# pwr.net
KiCad netlist of a schematic drawn in Altium Designer
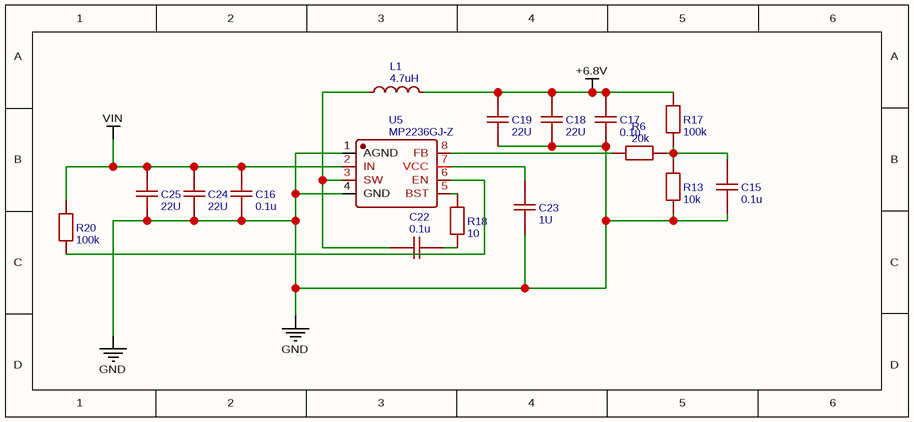
[diagram p0: pwr.schdoc]

(export (version "E")
  (design (tool "Eeschema 10.0.6"))
  (components
    (comp (ref "C15")
      (value "0.1u")
      (fields (field (name "CONTRIBUTOR") "LCEDA_Lib"))
      (libsource (lib "altium-import") (part "root_1_0.1u_"))
    )
    (comp (ref "C16")
      (value "0.1u")
      (fields (field (name "CONTRIBUTOR") "LCEDA_Lib"))
      (libsource (lib "altium-import") (part "root_1_0.1u_"))
    )
    (comp (ref "C17")
      (value "0.1u")
      (fields (field (name "CONTRIBUTOR") "LCEDA_Lib"))
      (libsource (lib "altium-import") (part "root_1_0.1u_"))
    )
    (comp (ref "C18")
      (value "22U")
      (fields (field (name "CONTRIBUTOR") "LCEDA_Lib"))
      (libsource (lib "altium-import") (part "root_1_22U_"))
    )
    (comp (ref "C19")
      (value "22U")
      (fields (field (name "CONTRIBUTOR") "LCEDA_Lib"))
      (libsource (lib "altium-import") (part "root_1_22U_"))
    )
    (comp (ref "C22")
      (value "0.1u")
      (fields (field (name "CONTRIBUTOR") "LCEDA_Lib"))
      (libsource (lib "altium-import") (part "root_0_0.1u_"))
    )
    (comp (ref "C23")
      (value "1U")
      (fields (field (name "CONTRIBUTOR") "LCEDA_Lib"))
      (libsource (lib "altium-import") (part "root_1_1U_"))
    )
    (comp (ref "C24")
      (value "22U")
      (fields (field (name "CONTRIBUTOR") "LCEDA_Lib"))
      (libsource (lib "altium-import") (part "root_1_22U_"))
    )
    (comp (ref "C25")
      (value "22U")
      (fields (field (name "CONTRIBUTOR") "LCEDA_Lib"))
      (libsource (lib "altium-import") (part "root_1_22U_"))
    )
    (comp (ref "L1")
      (value "4.7uH")
      (fields
        (field (name "BOM_MANUFACTURER PART") "SPM6530T-4R7M")
        (field (name "BOM_SUPPLIER PART") "C76857")
      )
      (libsource (lib "altium-import") (part "root_0_4.7uH_"))
    )
    (comp (ref "R6")
      (value "20k")
      (fields (field (name "CONTRIBUTOR") "LCEDA_Lib"))
      (libsource (lib "altium-import") (part "root_0_20k_"))
    )
    (comp (ref "R13")
      (value "10k")
      (fields (field (name "CONTRIBUTOR") "LCEDA_Lib"))
      (libsource (lib "altium-import") (part "root_1_10k_"))
    )
    (comp (ref "R17")
      (value "100k")
      (fields (field (name "CONTRIBUTOR") "LCEDA_Lib"))
      (libsource (lib "altium-import") (part "root_1_100k_"))
    )
    (comp (ref "R18")
      (value "10")
      (fields (field (name "CONTRIBUTOR") "LCEDA_Lib"))
      (libsource (lib "altium-import") (part "root_1_10_"))
    )
    (comp (ref "R20")
      (value "100k")
      (fields (field (name "CONTRIBUTOR") "LCEDA_Lib"))
      (libsource (lib "altium-import") (part "root_1_100k_"))
    )
    (comp (ref "U5")
      (value "MP2236GJ-Z")
      (fields (field (name "BOM_SUPPLIER PART") "C9900000708") (field (name "CONTRIBUTOR") "LCSC"))
      (libsource (lib "altium-import") (part "root_0_MP2236GJ-Z_"))
    )
  )
  (nets
    (net (code "1") (name "+6.8V") (class "Default")
      (node (ref "C17") (pin "2") (pinfunction "2_2") (pintype "passive"))
      (node (ref "C18") (pin "2") (pinfunction "2_2") (pintype "passive"))
      (node (ref "C19") (pin "2") (pinfunction "2_2") (pintype "passive"))
      (node (ref "L1") (pin "2") (pinfunction "2_2") (pintype "passive"))
      (node (ref "R17") (pin "2") (pinfunction "2_2") (pintype "passive"))
    )
    (net (code "2") (name "GND") (class "Default")
      (node (ref "C15") (pin "1") (pinfunction "1_1") (pintype "passive"))
      (node (ref "C16") (pin "1") (pinfunction "1_1") (pintype "passive"))
      (node (ref "C17") (pin "1") (pinfunction "1_1") (pintype "passive"))
      (node (ref "C18") (pin "1") (pinfunction "1_1") (pintype "passive"))
      (node (ref "C19") (pin "1") (pinfunction "1_1") (pintype "passive"))
      (node (ref "C23") (pin "1") (pinfunction "1_1") (pintype "passive"))
      (node (ref "C24") (pin "1") (pinfunction "1_1") (pintype "passive"))
      (node (ref "C25") (pin "1") (pinfunction "1_1") (pintype "passive"))
      (node (ref "R13") (pin "1") (pinfunction "1_1") (pintype "passive"))
      (node (ref "U5") (pin "1") (pinfunction "AGND_1") (pintype "passive"))
      (node (ref "U5") (pin "4") (pinfunction "GND_4") (pintype "passive"))
    )
    (net (code "3") (name "Net-(C15-Pad2)") (class "Default")
      (node (ref "C15") (pin "2") (pinfunction "2_2") (pintype "passive"))
      (node (ref "R13") (pin "2") (pinfunction "2_2") (pintype "passive"))
      (node (ref "R17") (pin "1") (pinfunction "1_1") (pintype "passive"))
      (node (ref "R6") (pin "2") (pinfunction "2_2") (pintype "passive"))
    )
    (net (code "4") (name "Net-(C22-Pad2)") (class "Default")
      (node (ref "C22") (pin "2") (pinfunction "2_2") (pintype "passive"))
      (node (ref "R18") (pin "1") (pinfunction "1_1") (pintype "passive"))
    )
    (net (code "5") (name "Net-(U5-BST)") (class "Default")
      (node (ref "R18") (pin "2") (pinfunction "2_2") (pintype "passive"))
      (node (ref "U5") (pin "5") (pinfunction "BST_5") (pintype "passive"))
    )
    (net (code "6") (name "Net-(U5-EN)") (class "Default")
      (node (ref "R20") (pin "1") (pinfunction "1_1") (pintype "passive"))
      (node (ref "U5") (pin "6") (pinfunction "EN_6") (pintype "passive"))
    )
    (net (code "7") (name "Net-(U5-FB)") (class "Default")
      (node (ref "R6") (pin "1") (pinfunction "1_1") (pintype "passive"))
      (node (ref "U5") (pin "8") (pinfunction "FB_8") (pintype "passive"))
    )
    (net (code "8") (name "Net-(U5-SW)") (class "Default")
      (node (ref "C22") (pin "1") (pinfunction "1_1") (pintype "passive"))
      (node (ref "L1") (pin "1") (pinfunction "1_1") (pintype "passive"))
      (node (ref "U5") (pin "3") (pinfunction "SW_3") (pintype "passive"))
    )
    (net (code "9") (name "Net-(U5-VCC)") (class "Default")
      (node (ref "C23") (pin "2") (pinfunction "2_2") (pintype "passive"))
      (node (ref "U5") (pin "7") (pinfunction "VCC_7") (pintype "passive"))
    )
    (net (code "10") (name "VIN") (class "Default")
      (node (ref "C16") (pin "2") (pinfunction "2_2") (pintype "passive"))
      (node (ref "C24") (pin "2") (pinfunction "2_2") (pintype "passive"))
      (node (ref "C25") (pin "2") (pinfunction "2_2") (pintype "passive"))
      (node (ref "R20") (pin "2") (pinfunction "2_2") (pintype "passive"))
      (node (ref "U5") (pin "2") (pinfunction "IN_2") (pintype "passive"))
    )
  )
)
